# Sheet2.net
KiCad netlist of a schematic drawn in Altium Designer
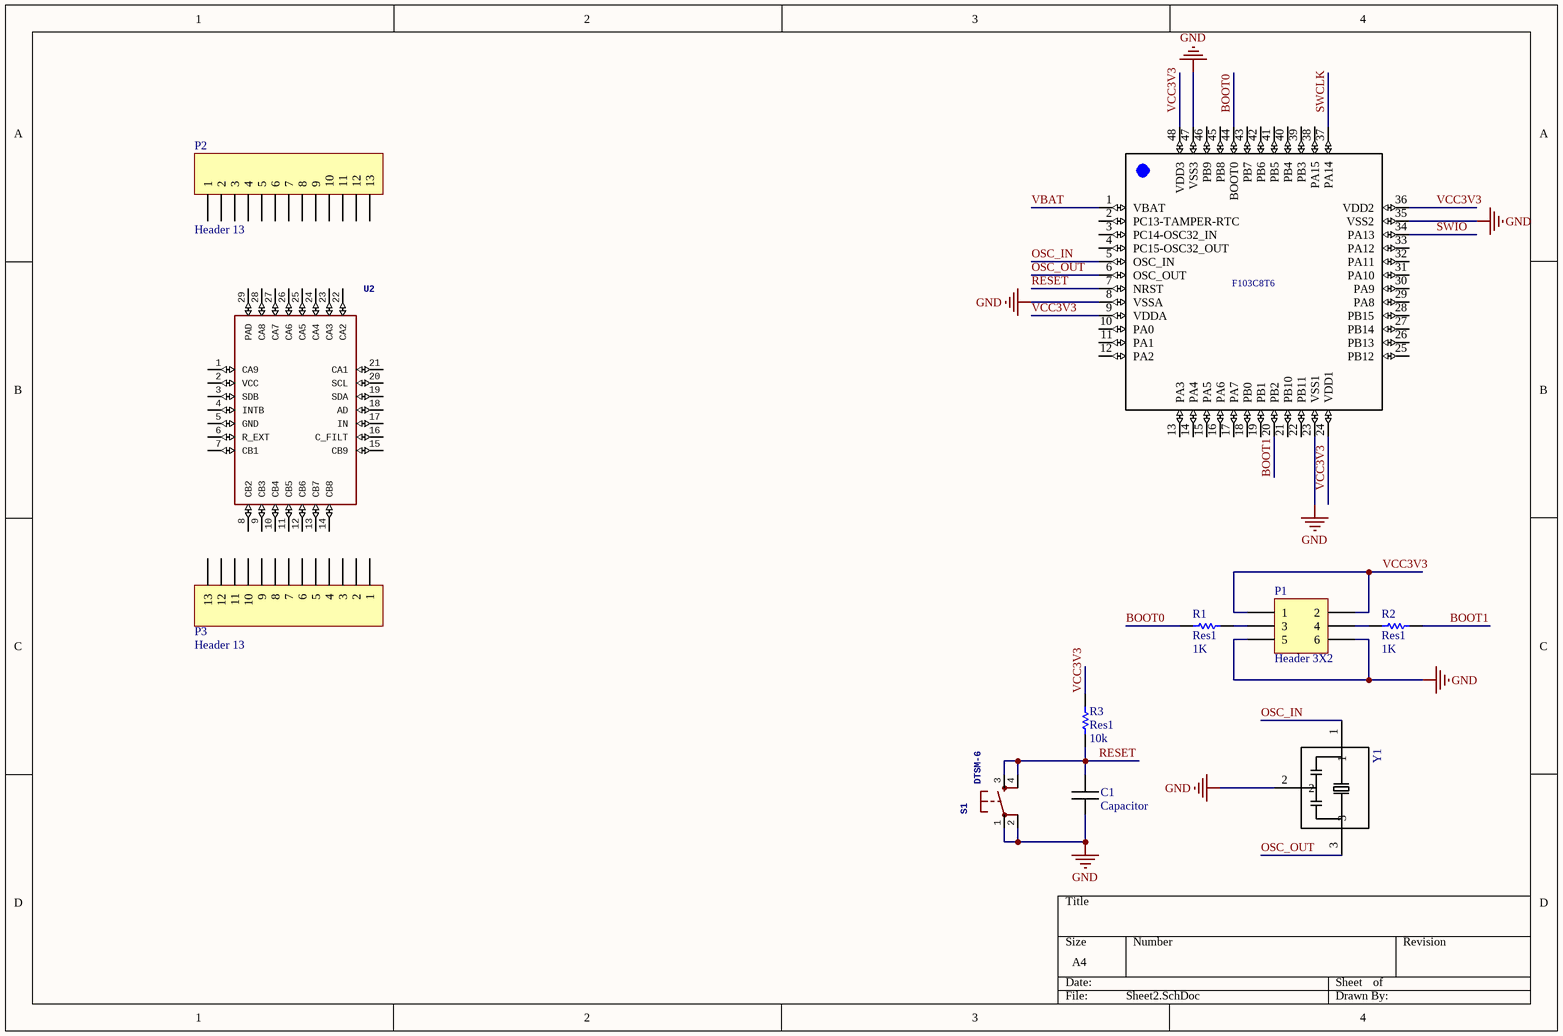
[diagram p0: Sheet2.SchDoc]

(export (version "E")
  (design (tool "Eeschema 10.0.6"))
  (components
    (comp (ref "C1")
      (value "Capacitor")
      (footprint "C 0603 / 1608")
      (libsource (lib "Standard") (part "Capacitor"))
    )
    (comp (ref "P1")
      (value "Header 3X2")
      (footprint "HDR2X3")
      (description "Header, 3-Pin, Dual row")
      (fields (field (name "PUBLISHER") "Altium Limited"))
      (libsource (lib "Miscellaneous Connectors") (part "Header 3X2"))
    )
    (comp (ref "P2")
      (value "Header 13")
      (footprint "HDR1X13")
      (description "Header, 13-Pin")
      (fields (field (name "PUBLISHER") "Altium Limited"))
      (libsource (lib "Miscellaneous Connectors") (part "Header 13"))
    )
    (comp (ref "P3")
      (value "Header 13")
      (footprint "HDR1X13")
      (description "Header, 13-Pin")
      (fields (field (name "PUBLISHER") "Altium Limited"))
      (libsource (lib "") (part "Header 13_1"))
    )
    (comp (ref "R1")
      (value "Res1")
      (footprint "C 0603 / 1608")
      (description "Resistor")
      (fields (field (name "ALTIUM_VALUE") "1K") (field (name "PUBLISHER") "Altium Limited"))
      (libsource (lib "Miscellaneous Devices") (part "Res1"))
    )
    (comp (ref "R2")
      (value "Res1")
      (footprint "C 0603 / 1608")
      (description "Resistor")
      (fields (field (name "ALTIUM_VALUE") "1K") (field (name "PUBLISHER") "Altium Limited"))
      (libsource (lib "Miscellaneous Devices") (part "Res1"))
    )
    (comp (ref "R3")
      (value "Res1")
      (footprint "C 0603 / 1608")
      (description "Resistor")
      (fields (field (name "ALTIUM_VALUE") "10k") (field (name "PUBLISHER") "Altium Limited"))
      (libsource (lib "Miscellaneous Devices") (part "Res1"))
    )
    (comp (ref "S1") (value "DTSM-6") (footprint "DTSM-6") (libsource (lib "Switches") (part "DTSM-6")))
    (comp (ref "U1")
      (value "STM32F103C8T6")
      (footprint "LQFP48_7X7MM_0.5MMPP")
      (fields (field (name "MF") "STMicroelectronics"))
      (libsource (lib "STM") (part "STM32F103C8T6"))
    )
    (comp (ref "U2")
      (value "LED Lighting Drivers LED Driver   Source:  Datasheet")
      (footprint "QFN40P400X400X80-29N")
      (fields (field (name "MANUFACTURER_PART_NUMBER") "IS31FL3731-QFLS2-TR"))
      (libsource (lib "IC") (part "IS31FL3731-QFLS2-TR"))
    )
    (comp (ref "Y1")
      (value "~")
      (footprint "OSC_CSTCE8M00G55-R0")
      (description "Ceramic Resonator 8MHz ??0.5% _Tol_ ??0.2% _Stability_ 33pF 40Ohm 3-Pin CSMD T/R")
      (fields (field (name "MF") "Murata") (field (name "MP") "CSTCE8M00G55-R0"))
      (libsource (lib "XTAL") (part "CSTCE8M00G55-R0"))
    )
  )
  (nets
    (net (code "1") (name "/BOOT0") (class "Default")
      (node (ref "R1") (pin "1") (pinfunction "1_1") (pintype "passive"))
      (node (ref "U1") (pin "44") (pinfunction "BOOT0_44") (pintype "bidirectional"))
    )
    (net (code "2") (name "/BOOT1") (class "Default")
      (node (ref "R2") (pin "2") (pinfunction "2_2") (pintype "passive"))
      (node (ref "U1") (pin "20") (pinfunction "PB2_20") (pintype "bidirectional"))
    )
    (net (code "3") (name "/OSC_IN") (class "Default")
      (node (ref "U1") (pin "5") (pinfunction "OSC_IN_5") (pintype "bidirectional"))
      (node (ref "Y1") (pin "1") (pinfunction "1_1") (pintype "passive"))
    )
    (net (code "4") (name "/OSC_OUT") (class "Default")
      (node (ref "U1") (pin "6") (pinfunction "OSC_OUT_6") (pintype "bidirectional"))
      (node (ref "Y1") (pin "3") (pinfunction "3_3") (pintype "passive"))
    )
    (net (code "5") (name "/RESET") (class "Default")
      (node (ref "C1") (pin "1") (pinfunction "1_1") (pintype "passive"))
      (node (ref "R3") (pin "2") (pinfunction "2_2") (pintype "passive"))
      (node (ref "S1") (pin "3") (pinfunction "3_3") (pintype "passive"))
      (node (ref "S1") (pin "4") (pinfunction "4_4") (pintype "passive"))
      (node (ref "U1") (pin "7") (pinfunction "NRST_7") (pintype "bidirectional"))
    )
    (net (code "6") (name "/SWCLK") (class "Default")
      (node (ref "U1") (pin "37") (pinfunction "PA14_37") (pintype "bidirectional"))
    )
    (net (code "7") (name "/SWIO") (class "Default")
      (node (ref "U1") (pin "34") (pinfunction "PA13_34") (pintype "bidirectional"))
    )
    (net (code "8") (name "/VBAT") (class "Default")
      (node (ref "U1") (pin "1") (pinfunction "VBAT_1") (pintype "bidirectional"))
    )
    (net (code "9") (name "/VCC3V3") (class "Default")
      (node (ref "P1") (pin "1") (pinfunction "1_1") (pintype "passive"))
      (node (ref "P1") (pin "2") (pinfunction "2_2") (pintype "passive"))
      (node (ref "R3") (pin "1") (pinfunction "1_1") (pintype "passive"))
      (node (ref "U1") (pin "24") (pinfunction "VDD1_24") (pintype "bidirectional"))
      (node (ref "U1") (pin "36") (pinfunction "VDD2_36") (pintype "bidirectional"))
      (node (ref "U1") (pin "48") (pinfunction "VDD3_48") (pintype "bidirectional"))
      (node (ref "U1") (pin "9") (pinfunction "VDDA_9") (pintype "bidirectional"))
    )
    (net (code "10") (name "GND") (class "Default")
      (node (ref "C1") (pin "2") (pinfunction "1_2") (pintype "passive"))
      (node (ref "P1") (pin "5") (pinfunction "5_5") (pintype "passive"))
      (node (ref "P1") (pin "6") (pinfunction "6_6") (pintype "passive"))
      (node (ref "S1") (pin "1") (pinfunction "1_1") (pintype "passive"))
      (node (ref "S1") (pin "2") (pinfunction "2_2") (pintype "passive"))
      (node (ref "U1") (pin "23") (pinfunction "VSS1_23") (pintype "bidirectional"))
      (node (ref "U1") (pin "35") (pinfunction "VSS2_35") (pintype "bidirectional"))
      (node (ref "U1") (pin "47") (pinfunction "VSS3_47") (pintype "bidirectional"))
      (node (ref "U1") (pin "8") (pinfunction "VSSA_8") (pintype "bidirectional"))
      (node (ref "Y1") (pin "2") (pinfunction "2_2") (pintype "power_in"))
    )
    (net (code "11") (name "Net-(P1-Pad3)") (class "Default")
      (node (ref "P1") (pin "3") (pinfunction "3_3") (pintype "passive"))
      (node (ref "R1") (pin "2") (pinfunction "2_2") (pintype "passive"))
    )
    (net (code "12") (name "Net-(P1-Pad4)") (class "Default")
      (node (ref "P1") (pin "4") (pinfunction "4_4") (pintype "passive"))
      (node (ref "R2") (pin "1") (pinfunction "1_1") (pintype "passive"))
    )
    (net (code "13") (name "unconnected-(P2-Pad1)") (class "Default")
      (node (ref "P2") (pin "1") (pinfunction "1_1") (pintype "passive"))
    )
    (net (code "14") (name "unconnected-(P2-Pad2)") (class "Default")
      (node (ref "P2") (pin "2") (pinfunction "2_2") (pintype "passive"))
    )
    (net (code "15") (name "unconnected-(P2-Pad3)") (class "Default")
      (node (ref "P2") (pin "3") (pinfunction "3_3") (pintype "passive"))
    )
    (net (code "16") (name "unconnected-(P2-Pad4)") (class "Default")
      (node (ref "P2") (pin "4") (pinfunction "4_4") (pintype "passive"))
    )
    (net (code "17") (name "unconnected-(P2-Pad5)") (class "Default")
      (node (ref "P2") (pin "5") (pinfunction "5_5") (pintype "passive"))
    )
    (net (code "18") (name "unconnected-(P2-Pad6)") (class "Default")
      (node (ref "P2") (pin "6") (pinfunction "6_6") (pintype "passive"))
    )
    (net (code "19") (name "unconnected-(P2-Pad7)") (class "Default")
      (node (ref "P2") (pin "7") (pinfunction "7_7") (pintype "passive"))
    )
    (net (code "20") (name "unconnected-(P2-Pad8)") (class "Default")
      (node (ref "P2") (pin "8") (pinfunction "8_8") (pintype "passive"))
    )
    (net (code "21") (name "unconnected-(P2-Pad9)") (class "Default")
      (node (ref "P2") (pin "9") (pinfunction "9_9") (pintype "passive"))
    )
    (net (code "22") (name "unconnected-(P2-Pad10)") (class "Default")
      (node (ref "P2") (pin "10") (pinfunction "10_10") (pintype "passive"))
    )
    (net (code "23") (name "unconnected-(P2-Pad11)") (class "Default")
      (node (ref "P2") (pin "11") (pinfunction "11_11") (pintype "passive"))
    )
    (net (code "24") (name "unconnected-(P2-Pad12)") (class "Default")
      (node (ref "P2") (pin "12") (pinfunction "12_12") (pintype "passive"))
    )
    (net (code "25") (name "unconnected-(P2-Pad13)") (class "Default")
      (node (ref "P2") (pin "13") (pinfunction "13_13") (pintype "passive"))
    )
    (net (code "26") (name "unconnected-(P3-Pad1)") (class "Default")
      (node (ref "P3") (pin "1") (pinfunction "1_1") (pintype "passive"))
    )
    (net (code "27") (name "unconnected-(P3-Pad2)") (class "Default")
      (node (ref "P3") (pin "2") (pinfunction "2_2") (pintype "passive"))
    )
    (net (code "28") (name "unconnected-(P3-Pad3)") (class "Default")
      (node (ref "P3") (pin "3") (pinfunction "3_3") (pintype "passive"))
    )
    (net (code "29") (name "unconnected-(P3-Pad4)") (class "Default")
      (node (ref "P3") (pin "4") (pinfunction "4_4") (pintype "passive"))
    )
    (net (code "30") (name "unconnected-(P3-Pad5)") (class "Default")
      (node (ref "P3") (pin "5") (pinfunction "5_5") (pintype "passive"))
    )
    (net (code "31") (name "unconnected-(P3-Pad6)") (class "Default")
      (node (ref "P3") (pin "6") (pinfunction "6_6") (pintype "passive"))
    )
    (net (code "32") (name "unconnected-(P3-Pad7)") (class "Default")
      (node (ref "P3") (pin "7") (pinfunction "7_7") (pintype "passive"))
    )
    (net (code "33") (name "unconnected-(P3-Pad8)") (class "Default")
      (node (ref "P3") (pin "8") (pinfunction "8_8") (pintype "passive"))
    )
    (net (code "34") (name "unconnected-(P3-Pad9)") (class "Default")
      (node (ref "P3") (pin "9") (pinfunction "9_9") (pintype "passive"))
    )
    (net (code "35") (name "unconnected-(P3-Pad10)") (class "Default")
      (node (ref "P3") (pin "10") (pinfunction "10_10") (pintype "passive"))
    )
    (net (code "36") (name "unconnected-(P3-Pad11)") (class "Default")
      (node (ref "P3") (pin "11") (pinfunction "11_11") (pintype "passive"))
    )
    (net (code "37") (name "unconnected-(P3-Pad12)") (class "Default")
      (node (ref "P3") (pin "12") (pinfunction "12_12") (pintype "passive"))
    )
    (net (code "38") (name "unconnected-(P3-Pad13)") (class "Default")
      (node (ref "P3") (pin "13") (pinfunction "13_13") (pintype "passive"))
    )
    (net (code "39") (name "unconnected-(U1-PA0-Pad10)") (class "Default")
      (node (ref "U1") (pin "10") (pinfunction "PA0_10") (pintype "bidirectional"))
    )
    (net (code "40") (name "unconnected-(U1-PA1-Pad11)") (class "Default")
      (node (ref "U1") (pin "11") (pinfunction "PA1_11") (pintype "bidirectional"))
    )
    (net (code "41") (name "unconnected-(U1-PA2-Pad12)") (class "Default")
      (node (ref "U1") (pin "12") (pinfunction "PA2_12") (pintype "bidirectional"))
    )
    (net (code "42") (name "unconnected-(U1-PA3-Pad13)") (class "Default")
      (node (ref "U1") (pin "13") (pinfunction "PA3_13") (pintype "bidirectional"))
    )
    (net (code "43") (name "unconnected-(U1-PA4-Pad14)") (class "Default")
      (node (ref "U1") (pin "14") (pinfunction "PA4_14") (pintype "bidirectional"))
    )
    (net (code "44") (name "unconnected-(U1-PA5-Pad15)") (class "Default")
      (node (ref "U1") (pin "15") (pinfunction "PA5_15") (pintype "bidirectional"))
    )
    (net (code "45") (name "unconnected-(U1-PA6-Pad16)") (class "Default")
      (node (ref "U1") (pin "16") (pinfunction "PA6_16") (pintype "bidirectional"))
    )
    (net (code "46") (name "unconnected-(U1-PA7-Pad17)") (class "Default")
      (node (ref "U1") (pin "17") (pinfunction "PA7_17") (pintype "bidirectional"))
    )
    (net (code "47") (name "unconnected-(U1-PA8-Pad29)") (class "Default")
      (node (ref "U1") (pin "29") (pinfunction "PA8_29") (pintype "bidirectional"))
    )
    (net (code "48") (name "unconnected-(U1-PA9-Pad30)") (class "Default")
      (node (ref "U1") (pin "30") (pinfunction "PA9_30") (pintype "bidirectional"))
    )
    (net (code "49") (name "unconnected-(U1-PA10-Pad31)") (class "Default")
      (node (ref "U1") (pin "31") (pinfunction "PA10_31") (pintype "bidirectional"))
    )
    (net (code "50") (name "unconnected-(U1-PA11-Pad32)") (class "Default")
      (node (ref "U1") (pin "32") (pinfunction "PA11_32") (pintype "bidirectional"))
    )
    (net (code "51") (name "unconnected-(U1-PA12-Pad33)") (class "Default")
      (node (ref "U1") (pin "33") (pinfunction "PA12_33") (pintype "bidirectional"))
    )
    (net (code "52") (name "unconnected-(U1-PA15-Pad38)") (class "Default")
      (node (ref "U1") (pin "38") (pinfunction "PA15_38") (pintype "bidirectional"))
    )
    (net (code "53") (name "unconnected-(U1-PB0-Pad18)") (class "Default")
      (node (ref "U1") (pin "18") (pinfunction "PB0_18") (pintype "bidirectional"))
    )
    (net (code "54") (name "unconnected-(U1-PB1-Pad19)") (class "Default")
      (node (ref "U1") (pin "19") (pinfunction "PB1_19") (pintype "bidirectional"))
    )
    (net (code "55") (name "unconnected-(U1-PB3-Pad39)") (class "Default")
      (node (ref "U1") (pin "39") (pinfunction "PB3_39") (pintype "bidirectional"))
    )
    (net (code "56") (name "unconnected-(U1-PB4-Pad40)") (class "Default")
      (node (ref "U1") (pin "40") (pinfunction "PB4_40") (pintype "bidirectional"))
    )
    (net (code "57") (name "unconnected-(U1-PB5-Pad41)") (class "Default")
      (node (ref "U1") (pin "41") (pinfunction "PB5_41") (pintype "bidirectional"))
    )
    (net (code "58") (name "unconnected-(U1-PB6-Pad42)") (class "Default")
      (node (ref "U1") (pin "42") (pinfunction "PB6_42") (pintype "bidirectional"))
    )
    (net (code "59") (name "unconnected-(U1-PB7-Pad43)") (class "Default")
      (node (ref "U1") (pin "43") (pinfunction "PB7_43") (pintype "bidirectional"))
    )
    (net (code "60") (name "unconnected-(U1-PB8-Pad45)") (class "Default")
      (node (ref "U1") (pin "45") (pinfunction "PB8_45") (pintype "bidirectional"))
    )
    (net (code "61") (name "unconnected-(U1-PB9-Pad46)") (class "Default")
      (node (ref "U1") (pin "46") (pinfunction "PB9_46") (pintype "bidirectional"))
    )
    (net (code "62") (name "unconnected-(U1-PB10-Pad21)") (class "Default")
      (node (ref "U1") (pin "21") (pinfunction "PB10_21") (pintype "bidirectional"))
    )
    (net (code "63") (name "unconnected-(U1-PB11-Pad22)") (class "Default")
      (node (ref "U1") (pin "22") (pinfunction "PB11_22") (pintype "bidirectional"))
    )
    (net (code "64") (name "unconnected-(U1-PB12-Pad25)") (class "Default")
      (node (ref "U1") (pin "25") (pinfunction "PB12_25") (pintype "bidirectional"))
    )
    (net (code "65") (name "unconnected-(U1-PB13-Pad26)") (class "Default")
      (node (ref "U1") (pin "26") (pinfunction "PB13_26") (pintype "bidirectional"))
    )
    (net (code "66") (name "unconnected-(U1-PB14-Pad27)") (class "Default")
      (node (ref "U1") (pin "27") (pinfunction "PB14_27") (pintype "bidirectional"))
    )
    (net (code "67") (name "unconnected-(U1-PB15-Pad28)") (class "Default")
      (node (ref "U1") (pin "28") (pinfunction "PB15_28") (pintype "bidirectional"))
    )
    (net (code "68") (name "unconnected-(U1-PC13-TAMPER-RTC-Pad2)") (class "Default")
      (node (ref "U1") (pin "2") (pinfunction "PC13-TAMPER-RTC_2") (pintype "bidirectional"))
    )
    (net (code "69") (name "unconnected-(U1-PC14-OSC32_IN-Pad3)") (class "Default")
      (node (ref "U1") (pin "3") (pinfunction "PC14-OSC32_IN_3") (pintype "bidirectional"))
    )
    (net (code "70") (name "unconnected-(U1-PC15-OSC32_OUT-Pad4)") (class "Default")
      (node (ref "U1") (pin "4") (pinfunction "PC15-OSC32_OUT_4") (pintype "bidirectional"))
    )
    (net (code "71") (name "unconnected-(U2-AD-Pad18)") (class "Default")
      (node (ref "U2") (pin "18") (pinfunction "AD_18") (pintype "bidirectional"))
    )
    (net (code "72") (name "unconnected-(U2-CA1-Pad21)") (class "Default")
      (node (ref "U2") (pin "21") (pinfunction "CA1_21") (pintype "bidirectional"))
    )
    (net (code "73") (name "unconnected-(U2-CA2-Pad22)") (class "Default")
      (node (ref "U2") (pin "22") (pinfunction "CA2_22") (pintype "bidirectional"))
    )
    (net (code "74") (name "unconnected-(U2-CA3-Pad23)") (class "Default")
      (node (ref "U2") (pin "23") (pinfunction "CA3_23") (pintype "bidirectional"))
    )
    (net (code "75") (name "unconnected-(U2-CA4-Pad24)") (class "Default")
      (node (ref "U2") (pin "24") (pinfunction "CA4_24") (pintype "bidirectional"))
    )
    (net (code "76") (name "unconnected-(U2-CA5-Pad25)") (class "Default")
      (node (ref "U2") (pin "25") (pinfunction "CA5_25") (pintype "bidirectional"))
    )
    (net (code "77") (name "unconnected-(U2-CA6-Pad26)") (class "Default")
      (node (ref "U2") (pin "26") (pinfunction "CA6_26") (pintype "bidirectional"))
    )
    (net (code "78") (name "unconnected-(U2-CA7-Pad27)") (class "Default")
      (node (ref "U2") (pin "27") (pinfunction "CA7_27") (pintype "bidirectional"))
    )
    (net (code "79") (name "unconnected-(U2-CA8-Pad28)") (class "Default")
      (node (ref "U2") (pin "28") (pinfunction "CA8_28") (pintype "bidirectional"))
    )
    (net (code "80") (name "unconnected-(U2-CA9-Pad1)") (class "Default")
      (node (ref "U2") (pin "1") (pinfunction "CA9_1") (pintype "bidirectional"))
    )
    (net (code "81") (name "unconnected-(U2-CB1-Pad7)") (class "Default")
      (node (ref "U2") (pin "7") (pinfunction "CB1_7") (pintype "bidirectional"))
    )
    (net (code "82") (name "unconnected-(U2-CB2-Pad8)") (class "Default")
      (node (ref "U2") (pin "8") (pinfunction "CB2_8") (pintype "bidirectional"))
    )
    (net (code "83") (name "unconnected-(U2-CB3-Pad9)") (class "Default")
      (node (ref "U2") (pin "9") (pinfunction "CB3_9") (pintype "bidirectional"))
    )
    (net (code "84") (name "unconnected-(U2-CB4-Pad10)") (class "Default")
      (node (ref "U2") (pin "10") (pinfunction "CB4_10") (pintype "bidirectional"))
    )
    (net (code "85") (name "unconnected-(U2-CB5-Pad11)") (class "Default")
      (node (ref "U2") (pin "11") (pinfunction "CB5_11") (pintype "bidirectional"))
    )
    (net (code "86") (name "unconnected-(U2-CB6-Pad12)") (class "Default")
      (node (ref "U2") (pin "12") (pinfunction "CB6_12") (pintype "bidirectional"))
    )
    (net (code "87") (name "unconnected-(U2-CB7-Pad13)") (class "Default")
      (node (ref "U2") (pin "13") (pinfunction "CB7_13") (pintype "bidirectional"))
    )
    (net (code "88") (name "unconnected-(U2-CB8-Pad14)") (class "Default")
      (node (ref "U2") (pin "14") (pinfunction "CB8_14") (pintype "bidirectional"))
    )
    (net (code "89") (name "unconnected-(U2-CB9-Pad15)") (class "Default")
      (node (ref "U2") (pin "15") (pinfunction "CB9_15") (pintype "bidirectional"))
    )
    (net (code "90") (name "unconnected-(U2-C_FILT-Pad16)") (class "Default")
      (node (ref "U2") (pin "16") (pinfunction "C_FILT_16") (pintype "bidirectional"))
    )
    (net (code "91") (name "unconnected-(U2-GND-Pad5)") (class "Default")
      (node (ref "U2") (pin "5") (pinfunction "GND_5") (pintype "bidirectional"))
    )
    (net (code "92") (name "unconnected-(U2-IN-Pad17)") (class "Default")
      (node (ref "U2") (pin "17") (pinfunction "IN_17") (pintype "bidirectional"))
    )
    (net (code "93") (name "unconnected-(U2-INTB-Pad4)") (class "Default")
      (node (ref "U2") (pin "4") (pinfunction "INTB_4") (pintype "bidirectional"))
    )
    (net (code "94") (name "unconnected-(U2-PAD-Pad29)") (class "Default")
      (node (ref "U2") (pin "29") (pinfunction "PAD_29") (pintype "bidirectional"))
    )
    (net (code "95") (name "unconnected-(U2-R_EXT-Pad6)") (class "Default")
      (node (ref "U2") (pin "6") (pinfunction "R_EXT_6") (pintype "bidirectional"))
    )
    (net (code "96") (name "unconnected-(U2-SCL-Pad20)") (class "Default")
      (node (ref "U2") (pin "20") (pinfunction "SCL_20") (pintype "bidirectional"))
    )
    (net (code "97") (name "unconnected-(U2-SDA-Pad19)") (class "Default")
      (node (ref "U2") (pin "19") (pinfunction "SDA_19") (pintype "bidirectional"))
    )
    (net (code "98") (name "unconnected-(U2-SDB-Pad3)") (class "Default")
      (node (ref "U2") (pin "3") (pinfunction "SDB_3") (pintype "bidirectional"))
    )
    (net (code "99") (name "unconnected-(U2-VCC-Pad2)") (class "Default")
      (node (ref "U2") (pin "2") (pinfunction "VCC_2") (pintype "bidirectional"))
    )
  )
)
